# Sheet1.net
KiCad netlist of a schematic drawn in Altium Designer
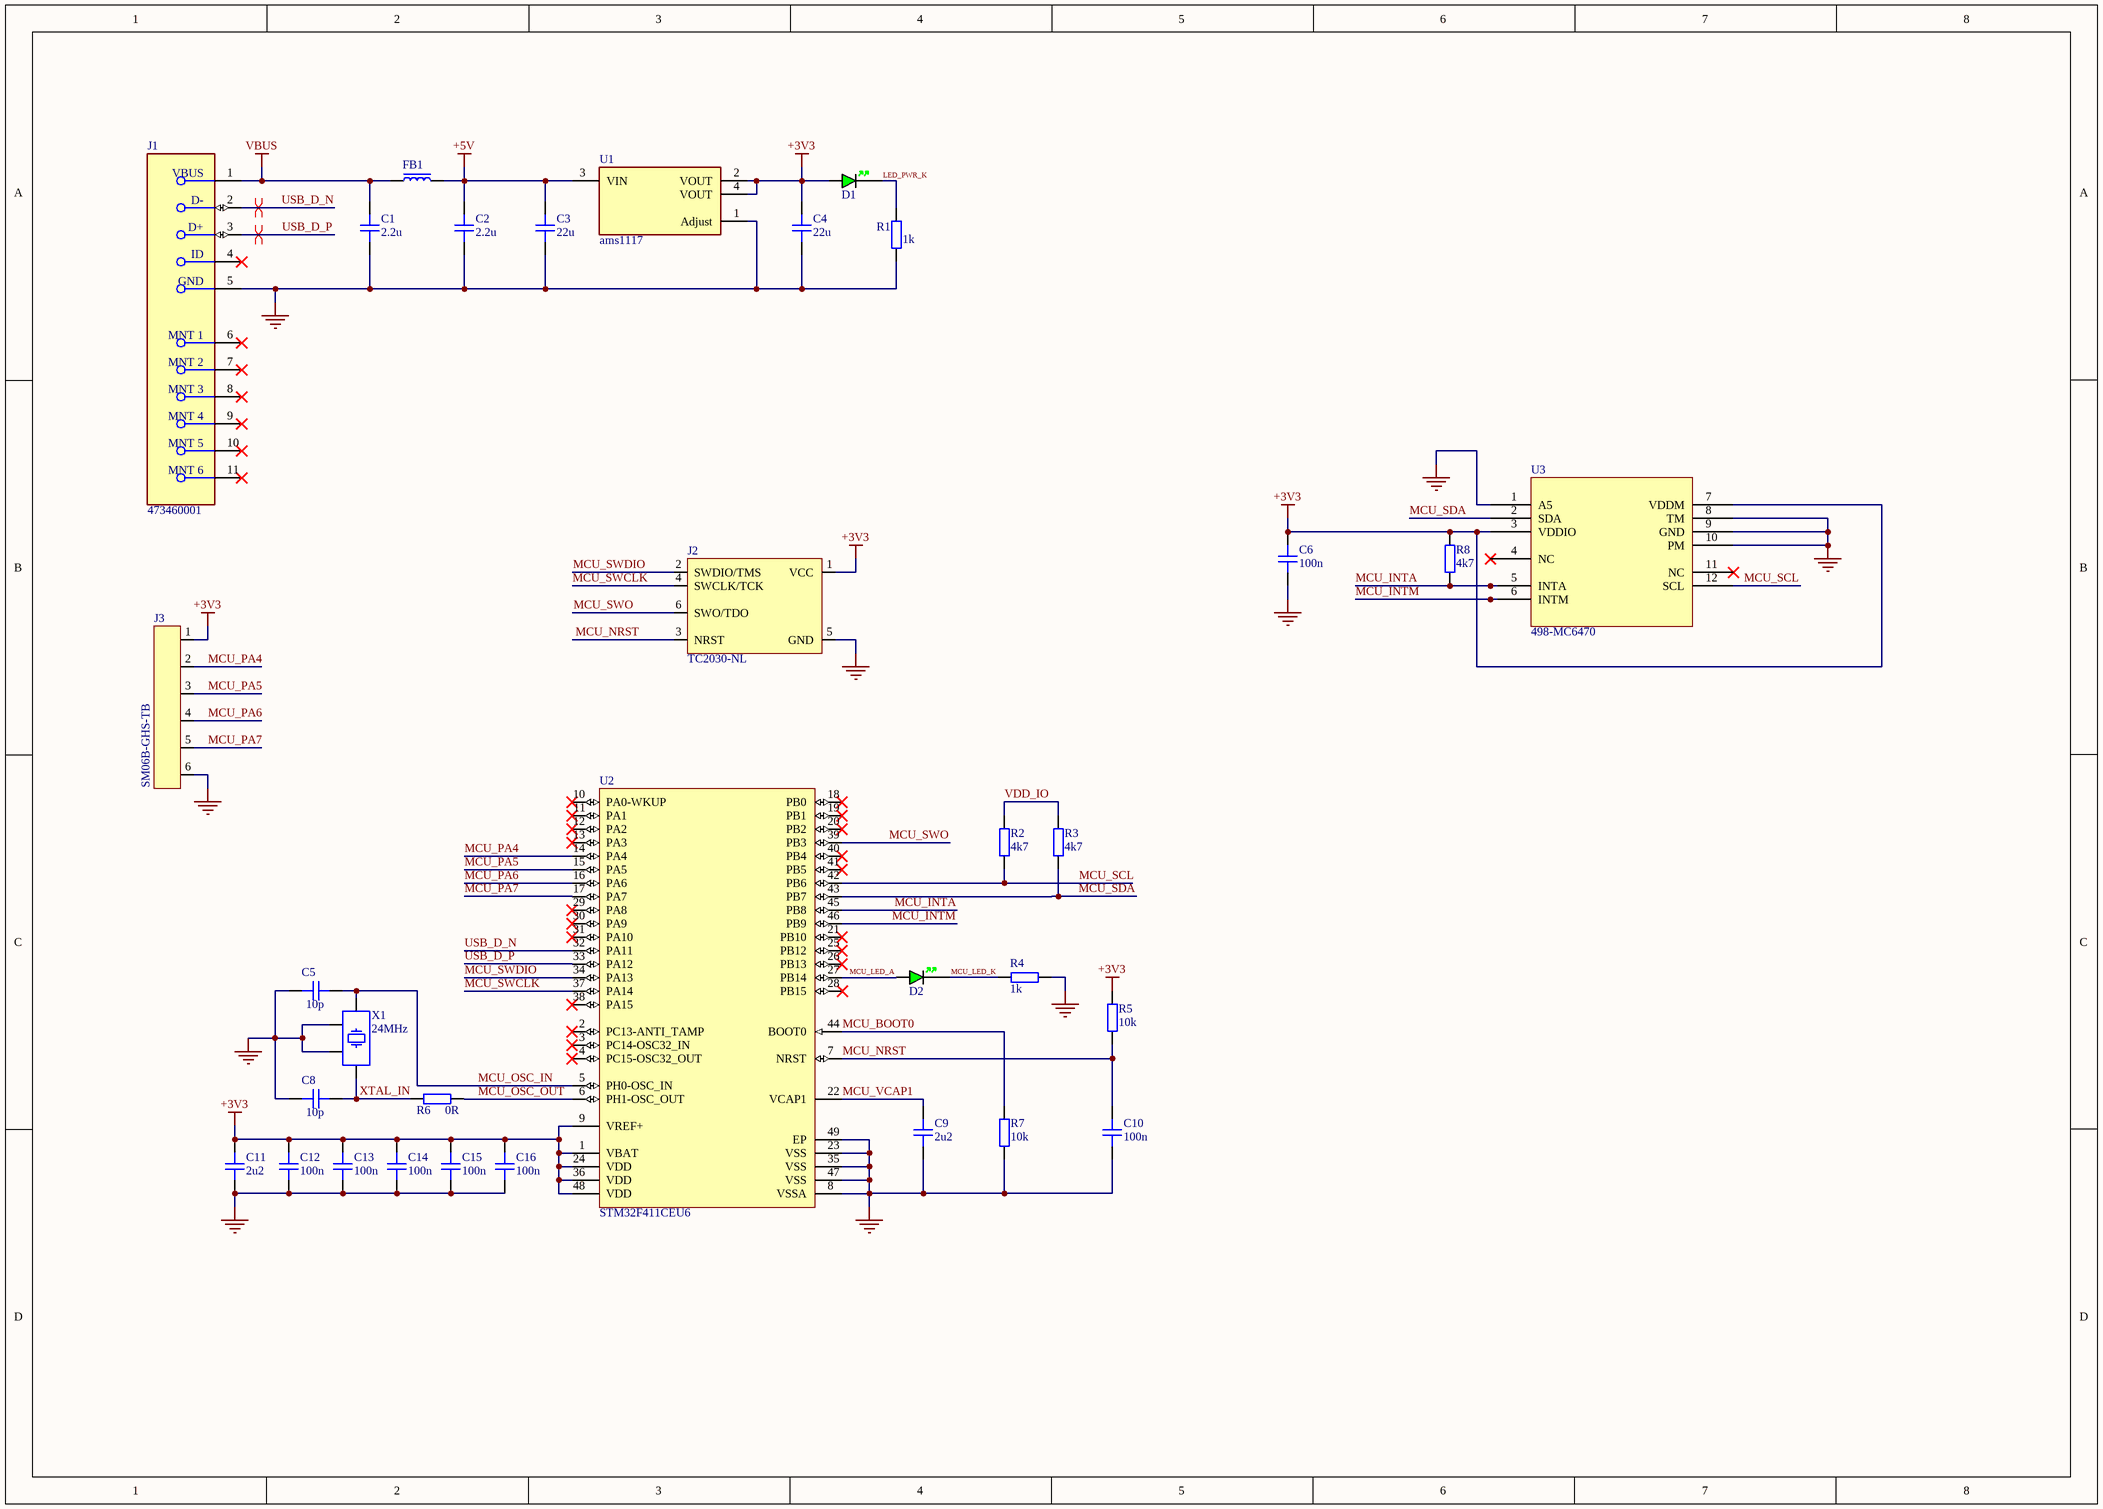
[diagram p0: Sheet1.SchDoc]

(export (version "E")
  (design (tool "Eeschema 10.0.6"))
  (components
    (comp (ref "C1")
      (value "2.2u")
      (footprint "CAP_0603")
      (description "Capacitor SMD 0603")
      (libsource (lib "Schematic-Lib-PhilsLab") (part "CAP_0603"))
    )
    (comp (ref "C2")
      (value "2.2u")
      (footprint "CAP_0603")
      (description "Capacitor SMD 0603")
      (libsource (lib "Schematic-Lib-PhilsLab") (part "CAP_0603"))
    )
    (comp (ref "C3")
      (value "22u")
      (footprint "CAP_0805")
      (description "Capacitor SMD 0805")
      (libsource (lib "Schematic-Lib-PhilsLab") (part "CAP_0805"))
    )
    (comp (ref "C4")
      (value "22u")
      (footprint "CAP_0805")
      (description "Capacitor SMD 0805")
      (libsource (lib "Schematic-Lib-PhilsLab") (part "CAP_0805"))
    )
    (comp (ref "C5")
      (value "10p")
      (footprint "CAP_0402")
      (description "Capacitor SMD 0402")
      (libsource (lib "Schematic-Lib-PhilsLab") (part "CAP_0402"))
    )
    (comp (ref "C6")
      (value "100n")
      (footprint "CAP_0402")
      (description "Capacitor SMD 0402")
      (libsource (lib "Schematic-Lib-PhilsLab") (part "CAP_0402"))
    )
    (comp (ref "C8")
      (value "10p")
      (footprint "CAP_0402")
      (description "Capacitor SMD 0402")
      (libsource (lib "Schematic-Lib-PhilsLab") (part "CAP_0402"))
    )
    (comp (ref "C9")
      (value "2u2")
      (footprint "CAP_0603")
      (description "Capacitor SMD 0603")
      (libsource (lib "Schematic-Lib-PhilsLab") (part "CAP_0603"))
    )
    (comp (ref "C10")
      (value "100n")
      (footprint "CAP_0402")
      (description "Capacitor SMD 0402")
      (libsource (lib "Schematic-Lib-PhilsLab") (part "CAP_0402"))
    )
    (comp (ref "C11")
      (value "2u2")
      (footprint "CAP_0603")
      (description "Capacitor SMD 0603")
      (libsource (lib "Schematic-Lib-PhilsLab") (part "CAP_0603"))
    )
    (comp (ref "C12")
      (value "100n")
      (footprint "CAP_0402")
      (description "Capacitor SMD 0402")
      (libsource (lib "Schematic-Lib-PhilsLab") (part "CAP_0402"))
    )
    (comp (ref "C13")
      (value "100n")
      (footprint "CAP_0402")
      (description "Capacitor SMD 0402")
      (libsource (lib "Schematic-Lib-PhilsLab") (part "CAP_0402"))
    )
    (comp (ref "C14")
      (value "100n")
      (footprint "CAP_0402")
      (description "Capacitor SMD 0402")
      (libsource (lib "Schematic-Lib-PhilsLab") (part "CAP_0402"))
    )
    (comp (ref "C15")
      (value "100n")
      (footprint "CAP_0402")
      (description "Capacitor SMD 0402")
      (libsource (lib "Schematic-Lib-PhilsLab") (part "CAP_0402"))
    )
    (comp (ref "C16")
      (value "100n")
      (footprint "CAP_0402")
      (description "Capacitor SMD 0402")
      (libsource (lib "Schematic-Lib-PhilsLab") (part "CAP_0402"))
    )
    (comp (ref "D1")
      (value "GREEN")
      (footprint "LED_0402_GREEN")
      (description "LED 0402 GREEN SMD")
      (libsource (lib "Schematic-Lib-PhilsLab") (part "LED_0402_GREEN"))
    )
    (comp (ref "D2")
      (value "GREEN")
      (footprint "LED_0402_GREEN")
      (description "LED 0402 GREEN SMD")
      (libsource (lib "Schematic-Lib-PhilsLab") (part "LED_0402_GREEN"))
    )
    (comp (ref "FB1")
      (value "FB0603")
      (footprint "FB_0603")
      (description "Ferrite Bead SMD 0603")
      (libsource (lib "Schematic-Lib-PhilsLab") (part "FB_0603"))
    )
    (comp (ref "J1")
      (value "473460001")
      (footprint "FP-473460001-MFG")
      (description "CONN RCPT USB2.0 MICRO B SMD R/A")
      (fields
        (field (name "OCTOPART") "https://octopart.com/47346-0001-molex-7164928")
        (field (name "MANUFACTURER") "Molex")
      )
      (libsource (lib "Altium Content Vault") (part "53ae1f1d9b557310b43ca686e5bb76a"))
    )
    (comp (ref "J2")
      (value "TC2030-NL")
      (footprint "TC2030-NL-FP")
      (description "Tag-Connect No-Solder SWD Debug Connector (No Legs) DO NOT PLACE")
      (fields
        (field (name "MANUFACTURER") "Tag-Connect")
        (field (name "MANUFACTURER PART NUMBER") "TC2030-NL-FP")
      )
      (libsource (lib "Schematic-Lib-PhilsLab") (part "TC2030-NL"))
    )
    (comp (ref "J3")
      (value "SM06B-GHS-TB")
      (footprint "SM06B-GHS-TB")
      (description "Header Connector 6 Position 1.25MM Pitch SMD Horizontal JST GH")
      (fields (field (name "MANUFACTURER") "JST"))
      (libsource (lib "Schematic-Lib-PhilsLab") (part "SM06B-GHS-TB"))
    )
    (comp (ref "R1")
      (value "1k")
      (footprint "RES_0402")
      (description "Resistor SMD 0402")
      (libsource (lib "Schematic-Lib-PhilsLab") (part "RES_0402"))
    )
    (comp (ref "R2")
      (value "4k7")
      (footprint "RES_0402")
      (description "Resistor SMD 0402")
      (libsource (lib "Schematic-Lib-PhilsLab") (part "RES_0402"))
    )
    (comp (ref "R3")
      (value "4k7")
      (footprint "RES_0402")
      (description "Resistor SMD 0402")
      (libsource (lib "Schematic-Lib-PhilsLab") (part "RES_0402"))
    )
    (comp (ref "R4")
      (value "1k")
      (footprint "RES_0402")
      (description "Resistor SMD 0402")
      (libsource (lib "Schematic-Lib-PhilsLab") (part "RES_0402"))
    )
    (comp (ref "R5")
      (value "10k")
      (footprint "RES_0402")
      (description "Resistor SMD 0402")
      (libsource (lib "Schematic-Lib-PhilsLab") (part "RES_0402"))
    )
    (comp (ref "R6")
      (value "0R")
      (footprint "RES_0402")
      (description "Resistor SMD 0402")
      (libsource (lib "Schematic-Lib-PhilsLab") (part "RES_0402"))
    )
    (comp (ref "R7")
      (value "10k")
      (footprint "RES_0402")
      (description "Resistor SMD 0402")
      (libsource (lib "Schematic-Lib-PhilsLab") (part "RES_0402"))
    )
    (comp (ref "R8")
      (value "4k7")
      (footprint "RES_0402")
      (description "Resistor SMD 0402")
      (libsource (lib "Schematic-Lib-PhilsLab") (part "RES_0402"))
    )
    (comp (ref "U1")
      (value "ams1117")
      (footprint "FP-ams1117-IPC_C")
      (description "1A LOW DROPOUT VOLTAGE REGULATOR")
      (libsource (lib "Altium Content Vault") (part "59ad430b93a2c51b3e6ee7c3b069677"))
    )
    (comp (ref "U2")
      (value "STM32F411CEU6")
      (footprint "STM-UFQFPN48_L")
      (libsource (lib "Altium Content Vault") (part "MC-ARM-STM32F411-UFQFPN48"))
    )
    (comp (ref "U3")
      (value "498-MC6470")
      (footprint "MC6470")
      (description "IMUs - Inertial Measurement Units 8g, 14-Bit Output 6-Axis eCompass")
      (libsource (lib "Schematic-Lib-PhilsLab") (part "MC6470"))
    )
    (comp (ref "X1")
      (value "24MHz")
      (footprint "XTAL_3225")
      (description "Crystal SMD 24MHz 10PPM 7pF 3225")
      (fields
        (field (name "MANUFACTURER") "Epson")
        (field (name "MANUFACTURER PART NUMBER") "TSX-3225 24.0000MF15X-AC")
      )
      (libsource (lib "Schematic-Lib-PhilsLab") (part "TSX-3225_24.0000MF15X-AC"))
    )
  )
  (nets
    (net (code "1") (name "+3V3") (class "Default")
      (node (ref "C11") (pin "2") (pinfunction "2_2") (pintype "passive"))
      (node (ref "C12") (pin "2") (pinfunction "2_2") (pintype "passive"))
      (node (ref "C13") (pin "2") (pinfunction "2_2") (pintype "passive"))
      (node (ref "C14") (pin "2") (pinfunction "2_2") (pintype "passive"))
      (node (ref "C15") (pin "2") (pinfunction "2_2") (pintype "passive"))
      (node (ref "C16") (pin "2") (pinfunction "2_2") (pintype "passive"))
      (node (ref "C4") (pin "2") (pinfunction "2_2") (pintype "passive"))
      (node (ref "C6") (pin "2") (pinfunction "2_2") (pintype "passive"))
      (node (ref "D1") (pin "A") (pinfunction "A_A") (pintype "passive"))
      (node (ref "J2") (pin "1") (pinfunction "VCC_1") (pintype "passive"))
      (node (ref "J3") (pin "1") (pinfunction "1_1") (pintype "passive"))
      (node (ref "R5") (pin "2") (pinfunction "2_2") (pintype "passive"))
      (node (ref "R8") (pin "2") (pinfunction "2_2") (pintype "passive"))
      (node (ref "U1") (pin "2") (pinfunction "VOUT_2") (pintype "passive"))
      (node (ref "U1") (pin "4") (pinfunction "VOUT_4") (pintype "passive"))
      (node (ref "U2") (pin "1") (pinfunction "VBAT_1") (pintype "power_in"))
      (node (ref "U2") (pin "24") (pinfunction "VDD_24") (pintype "power_in"))
      (node (ref "U2") (pin "36") (pinfunction "VDD_36") (pintype "power_in"))
      (node (ref "U2") (pin "48") (pinfunction "VDD_48") (pintype "power_in"))
      (node (ref "U2") (pin "9") (pinfunction "VREF+_9") (pintype "power_in"))
      (node (ref "U3") (pin "3") (pinfunction "VDDIO_3") (pintype "passive"))
      (node (ref "U3") (pin "7") (pinfunction "VDDM_7") (pintype "passive"))
    )
    (net (code "2") (name "+5V") (class "Default")
      (node (ref "C2") (pin "2") (pinfunction "2_2") (pintype "passive"))
      (node (ref "C3") (pin "2") (pinfunction "2_2") (pintype "passive"))
      (node (ref "FB1") (pin "2") (pinfunction "2_2") (pintype "passive"))
      (node (ref "U1") (pin "3") (pinfunction "VIN_3") (pintype "power_in"))
    )
    (net (code "3") (name "/LED_PWR_K") (class "Default")
      (node (ref "D1") (pin "K") (pinfunction "K_K") (pintype "passive"))
      (node (ref "R1") (pin "2") (pinfunction "2_2") (pintype "passive"))
    )
    (net (code "4") (name "/MCU_BOOT0") (class "Default")
      (node (ref "R7") (pin "2") (pinfunction "2_2") (pintype "passive"))
      (node (ref "U2") (pin "44") (pinfunction "BOOT0_44") (pintype "input"))
    )
    (net (code "5") (name "/MCU_INTA") (class "Default")
      (node (ref "R8") (pin "1") (pinfunction "1_1") (pintype "passive"))
      (node (ref "U2") (pin "45") (pinfunction "PB8_45") (pintype "bidirectional"))
      (node (ref "U3") (pin "5") (pinfunction "INTA_5") (pintype "passive"))
    )
    (net (code "6") (name "/MCU_INTM") (class "Default")
      (node (ref "U2") (pin "46") (pinfunction "PB9_46") (pintype "bidirectional"))
      (node (ref "U3") (pin "6") (pinfunction "INTM_6") (pintype "passive"))
    )
    (net (code "7") (name "/MCU_LED_A") (class "Default")
      (node (ref "D2") (pin "A") (pinfunction "A_A") (pintype "passive"))
      (node (ref "U2") (pin "27") (pinfunction "PB14_27") (pintype "bidirectional"))
    )
    (net (code "8") (name "/MCU_LED_K") (class "Default")
      (node (ref "D2") (pin "K") (pinfunction "K_K") (pintype "passive"))
      (node (ref "R4") (pin "1") (pinfunction "1_1") (pintype "passive"))
    )
    (net (code "9") (name "/MCU_NRST") (class "Default")
      (node (ref "C10") (pin "2") (pinfunction "2_2") (pintype "passive"))
      (node (ref "J2") (pin "3") (pinfunction "NRST_3") (pintype "passive"))
      (node (ref "R5") (pin "1") (pinfunction "1_1") (pintype "passive"))
      (node (ref "U2") (pin "7") (pinfunction "NRST_7") (pintype "bidirectional"))
    )
    (net (code "10") (name "/MCU_OSC_IN") (class "Default")
      (node (ref "C5") (pin "2") (pinfunction "2_2") (pintype "passive"))
      (node (ref "U2") (pin "5") (pinfunction "PH0-OSC_IN_5") (pintype "bidirectional"))
      (node (ref "X1") (pin "1") (pinfunction "1_1") (pintype "passive"))
    )
    (net (code "11") (name "/MCU_OSC_OUT") (class "Default")
      (node (ref "R6") (pin "2") (pinfunction "2_2") (pintype "passive"))
      (node (ref "U2") (pin "6") (pinfunction "PH1-OSC_OUT_6") (pintype "bidirectional"))
    )
    (net (code "12") (name "/MCU_PA4") (class "Default")
      (node (ref "J3") (pin "2") (pinfunction "2_2") (pintype "passive"))
      (node (ref "U2") (pin "14") (pinfunction "PA4_14") (pintype "bidirectional"))
    )
    (net (code "13") (name "/MCU_PA5") (class "Default")
      (node (ref "J3") (pin "3") (pinfunction "3_3") (pintype "passive"))
      (node (ref "U2") (pin "15") (pinfunction "PA5_15") (pintype "bidirectional"))
    )
    (net (code "14") (name "/MCU_PA6") (class "Default")
      (node (ref "J3") (pin "4") (pinfunction "4_4") (pintype "passive"))
      (node (ref "U2") (pin "16") (pinfunction "PA6_16") (pintype "bidirectional"))
    )
    (net (code "15") (name "/MCU_PA7") (class "Default")
      (node (ref "J3") (pin "5") (pinfunction "5_5") (pintype "passive"))
      (node (ref "U2") (pin "17") (pinfunction "PA7_17") (pintype "bidirectional"))
    )
    (net (code "16") (name "/MCU_SCL") (class "Default")
      (node (ref "R2") (pin "1") (pinfunction "1_1") (pintype "passive"))
      (node (ref "U2") (pin "42") (pinfunction "PB6_42") (pintype "bidirectional"))
      (node (ref "U3") (pin "12") (pinfunction "SCL_12") (pintype "passive"))
    )
    (net (code "17") (name "/MCU_SDA") (class "Default")
      (node (ref "R3") (pin "1") (pinfunction "1_1") (pintype "passive"))
      (node (ref "U2") (pin "43") (pinfunction "PB7_43") (pintype "bidirectional"))
      (node (ref "U3") (pin "2") (pinfunction "SDA_2") (pintype "passive"))
    )
    (net (code "18") (name "/MCU_SWCLK") (class "Default")
      (node (ref "J2") (pin "4") (pinfunction "SWCLK/TCK_4") (pintype "passive"))
      (node (ref "U2") (pin "37") (pinfunction "PA14_37") (pintype "bidirectional"))
    )
    (net (code "19") (name "/MCU_SWDIO") (class "Default")
      (node (ref "J2") (pin "2") (pinfunction "SWDIO/TMS_2") (pintype "passive"))
      (node (ref "U2") (pin "34") (pinfunction "PA13_34") (pintype "bidirectional"))
    )
    (net (code "20") (name "/MCU_SWO") (class "Default")
      (node (ref "J2") (pin "6") (pinfunction "SWO/TDO_6") (pintype "passive"))
      (node (ref "U2") (pin "39") (pinfunction "PB3_39") (pintype "bidirectional"))
    )
    (net (code "21") (name "/MCU_VCAP1") (class "Default")
      (node (ref "C9") (pin "2") (pinfunction "2_2") (pintype "passive"))
      (node (ref "U2") (pin "22") (pinfunction "VCAP1_22") (pintype "passive"))
    )
    (net (code "22") (name "/USB_D_N") (class "Default")
      (node (ref "J1") (pin "2") (pinfunction "D-_2") (pintype "bidirectional"))
      (node (ref "U2") (pin "32") (pinfunction "PA11_32") (pintype "bidirectional"))
    )
    (net (code "23") (name "/USB_D_P") (class "Default")
      (node (ref "J1") (pin "3") (pinfunction "D+_3") (pintype "bidirectional"))
      (node (ref "U2") (pin "33") (pinfunction "PA12_33") (pintype "bidirectional"))
    )
    (net (code "24") (name "/VDD_IO") (class "Default")
      (node (ref "R2") (pin "2") (pinfunction "2_2") (pintype "passive"))
      (node (ref "R3") (pin "2") (pinfunction "2_2") (pintype "passive"))
    )
    (net (code "25") (name "/XTAL_IN") (class "Default")
      (node (ref "C8") (pin "2") (pinfunction "2_2") (pintype "passive"))
      (node (ref "R6") (pin "1") (pinfunction "1_1") (pintype "passive"))
      (node (ref "X1") (pin "3") (pinfunction "3_3") (pintype "passive"))
    )
    (net (code "26") (name "GND") (class "Default")
      (node (ref "C1") (pin "1") (pinfunction "1_1") (pintype "passive"))
      (node (ref "C10") (pin "1") (pinfunction "1_1") (pintype "passive"))
      (node (ref "C11") (pin "1") (pinfunction "1_1") (pintype "passive"))
      (node (ref "C12") (pin "1") (pinfunction "1_1") (pintype "passive"))
      (node (ref "C13") (pin "1") (pinfunction "1_1") (pintype "passive"))
      (node (ref "C14") (pin "1") (pinfunction "1_1") (pintype "passive"))
      (node (ref "C15") (pin "1") (pinfunction "1_1") (pintype "passive"))
      (node (ref "C16") (pin "1") (pinfunction "1_1") (pintype "passive"))
      (node (ref "C2") (pin "1") (pinfunction "1_1") (pintype "passive"))
      (node (ref "C3") (pin "1") (pinfunction "1_1") (pintype "passive"))
      (node (ref "C4") (pin "1") (pinfunction "1_1") (pintype "passive"))
      (node (ref "C5") (pin "1") (pinfunction "1_1") (pintype "passive"))
      (node (ref "C6") (pin "1") (pinfunction "1_1") (pintype "passive"))
      (node (ref "C8") (pin "1") (pinfunction "1_1") (pintype "passive"))
      (node (ref "C9") (pin "1") (pinfunction "1_1") (pintype "passive"))
      (node (ref "J1") (pin "5") (pinfunction "GND_5") (pintype "power_in"))
      (node (ref "J2") (pin "5") (pinfunction "GND_5") (pintype "passive"))
      (node (ref "J3") (pin "6") (pinfunction "6_6") (pintype "passive"))
      (node (ref "R1") (pin "1") (pinfunction "1_1") (pintype "passive"))
      (node (ref "R4") (pin "2") (pinfunction "2_2") (pintype "passive"))
      (node (ref "R7") (pin "1") (pinfunction "1_1") (pintype "passive"))
      (node (ref "U1") (pin "1") (pinfunction "Adjust_1") (pintype "passive"))
      (node (ref "U2") (pin "23") (pinfunction "VSS_23") (pintype "power_in"))
      (node (ref "U2") (pin "35") (pinfunction "VSS_35") (pintype "power_in"))
      (node (ref "U2") (pin "47") (pinfunction "VSS_47") (pintype "power_in"))
      (node (ref "U2") (pin "49") (pinfunction "EP_49") (pintype "power_in"))
      (node (ref "U2") (pin "8") (pinfunction "VSSA_8") (pintype "power_in"))
      (node (ref "U3") (pin "1") (pinfunction "A5_1") (pintype "passive"))
      (node (ref "U3") (pin "10") (pinfunction "PM_10") (pintype "passive"))
      (node (ref "U3") (pin "8") (pinfunction "TM_8") (pintype "passive"))
      (node (ref "U3") (pin "9") (pinfunction "GND_9") (pintype "passive"))
      (node (ref "X1") (pin "2") (pinfunction "2_2") (pintype "passive"))
      (node (ref "X1") (pin "4") (pinfunction "4_4") (pintype "passive"))
    )
    (net (code "27") (name "VBUS") (class "Default")
      (node (ref "C1") (pin "2") (pinfunction "2_2") (pintype "passive"))
      (node (ref "FB1") (pin "1") (pinfunction "1_1") (pintype "passive"))
      (node (ref "J1") (pin "1") (pinfunction "VBUS_1") (pintype "power_in"))
    )
    (net (code "28") (name "unconnected-(J1-ID-Pad4)") (class "Default")
      (node (ref "J1") (pin "4") (pinfunction "ID_4") (pintype "passive+no_connect"))
    )
    (net (code "29") (name "unconnected-(J1-MNT_1-Pad6)") (class "Default")
      (node (ref "J1") (pin "6") (pinfunction "MNT_1_6") (pintype "passive+no_connect"))
    )
    (net (code "30") (name "unconnected-(J1-MNT_2-Pad7)") (class "Default")
      (node (ref "J1") (pin "7") (pinfunction "MNT_2_7") (pintype "passive+no_connect"))
    )
    (net (code "31") (name "unconnected-(J1-MNT_3-Pad8)") (class "Default")
      (node (ref "J1") (pin "8") (pinfunction "MNT_3_8") (pintype "passive+no_connect"))
    )
    (net (code "32") (name "unconnected-(J1-MNT_4-Pad9)") (class "Default")
      (node (ref "J1") (pin "9") (pinfunction "MNT_4_9") (pintype "passive+no_connect"))
    )
    (net (code "33") (name "unconnected-(J1-MNT_5-Pad10)") (class "Default")
      (node (ref "J1") (pin "10") (pinfunction "MNT_5_10") (pintype "passive+no_connect"))
    )
    (net (code "34") (name "unconnected-(J1-MNT_6-Pad11)") (class "Default")
      (node (ref "J1") (pin "11") (pinfunction "MNT_6_11") (pintype "passive+no_connect"))
    )
    (net (code "35") (name "unconnected-(U2-PA0-WKUP-Pad10)") (class "Default")
      (node (ref "U2") (pin "10") (pinfunction "PA0-WKUP_10") (pintype "bidirectional+no_connect"))
    )
    (net (code "36") (name "unconnected-(U2-PA1-Pad11)") (class "Default")
      (node (ref "U2") (pin "11") (pinfunction "PA1_11") (pintype "bidirectional+no_connect"))
    )
    (net (code "37") (name "unconnected-(U2-PA2-Pad12)") (class "Default")
      (node (ref "U2") (pin "12") (pinfunction "PA2_12") (pintype "bidirectional+no_connect"))
    )
    (net (code "38") (name "unconnected-(U2-PA3-Pad13)") (class "Default")
      (node (ref "U2") (pin "13") (pinfunction "PA3_13") (pintype "bidirectional+no_connect"))
    )
    (net (code "39") (name "unconnected-(U2-PA8-Pad29)") (class "Default")
      (node (ref "U2") (pin "29") (pinfunction "PA8_29") (pintype "bidirectional+no_connect"))
    )
    (net (code "40") (name "unconnected-(U2-PA9-Pad30)") (class "Default")
      (node (ref "U2") (pin "30") (pinfunction "PA9_30") (pintype "bidirectional+no_connect"))
    )
    (net (code "41") (name "unconnected-(U2-PA10-Pad31)") (class "Default")
      (node (ref "U2") (pin "31") (pinfunction "PA10_31") (pintype "bidirectional+no_connect"))
    )
    (net (code "42") (name "unconnected-(U2-PA15-Pad38)") (class "Default")
      (node (ref "U2") (pin "38") (pinfunction "PA15_38") (pintype "bidirectional+no_connect"))
    )
    (net (code "43") (name "unconnected-(U2-PB0-Pad18)") (class "Default")
      (node (ref "U2") (pin "18") (pinfunction "PB0_18") (pintype "bidirectional+no_connect"))
    )
    (net (code "44") (name "unconnected-(U2-PB1-Pad19)") (class "Default")
      (node (ref "U2") (pin "19") (pinfunction "PB1_19") (pintype "bidirectional+no_connect"))
    )
    (net (code "45") (name "unconnected-(U2-PB2-Pad20)") (class "Default")
      (node (ref "U2") (pin "20") (pinfunction "PB2_20") (pintype "bidirectional+no_connect"))
    )
    (net (code "46") (name "unconnected-(U2-PB4-Pad40)") (class "Default")
      (node (ref "U2") (pin "40") (pinfunction "PB4_40") (pintype "bidirectional+no_connect"))
    )
    (net (code "47") (name "unconnected-(U2-PB5-Pad41)") (class "Default")
      (node (ref "U2") (pin "41") (pinfunction "PB5_41") (pintype "bidirectional+no_connect"))
    )
    (net (code "48") (name "unconnected-(U2-PB10-Pad21)") (class "Default")
      (node (ref "U2") (pin "21") (pinfunction "PB10_21") (pintype "bidirectional+no_connect"))
    )
    (net (code "49") (name "unconnected-(U2-PB12-Pad25)") (class "Default")
      (node (ref "U2") (pin "25") (pinfunction "PB12_25") (pintype "bidirectional+no_connect"))
    )
    (net (code "50") (name "unconnected-(U2-PB13-Pad26)") (class "Default")
      (node (ref "U2") (pin "26") (pinfunction "PB13_26") (pintype "bidirectional+no_connect"))
    )
    (net (code "51") (name "unconnected-(U2-PB15-Pad28)") (class "Default")
      (node (ref "U2") (pin "28") (pinfunction "PB15_28") (pintype "bidirectional+no_connect"))
    )
    (net (code "52") (name "unconnected-(U2-PC13-ANTI_TAMP-Pad2)") (class "Default")
      (node (ref "U2") (pin "2") (pinfunction "PC13-ANTI_TAMP_2") (pintype "bidirectional+no_connect"))
    )
    (net (code "53") (name "unconnected-(U2-PC14-OSC32_IN-Pad3)") (class "Default")
      (node (ref "U2") (pin "3") (pinfunction "PC14-OSC32_IN_3") (pintype "bidirectional+no_connect"))
    )
    (net (code "54") (name "unconnected-(U2-PC15-OSC32_OUT-Pad4)") (class "Default")
      (node (ref "U2") (pin "4") (pinfunction "PC15-OSC32_OUT_4") (pintype "bidirectional+no_connect"))
    )
    (net (code "55") (name "unconnected-(U3-NC-Pad4)") (class "Default")
      (node (ref "U3") (pin "4") (pinfunction "NC_4") (pintype "passive+no_connect"))
    )
    (net (code "56") (name "unconnected-(U3-NC-Pad11)") (class "Default")
      (node (ref "U3") (pin "11") (pinfunction "NC_11") (pintype "passive+no_connect"))
    )
  )
)
